# EPROM_Programmer_2.net
KiCad netlist of a schematic drawn in Altium Designer
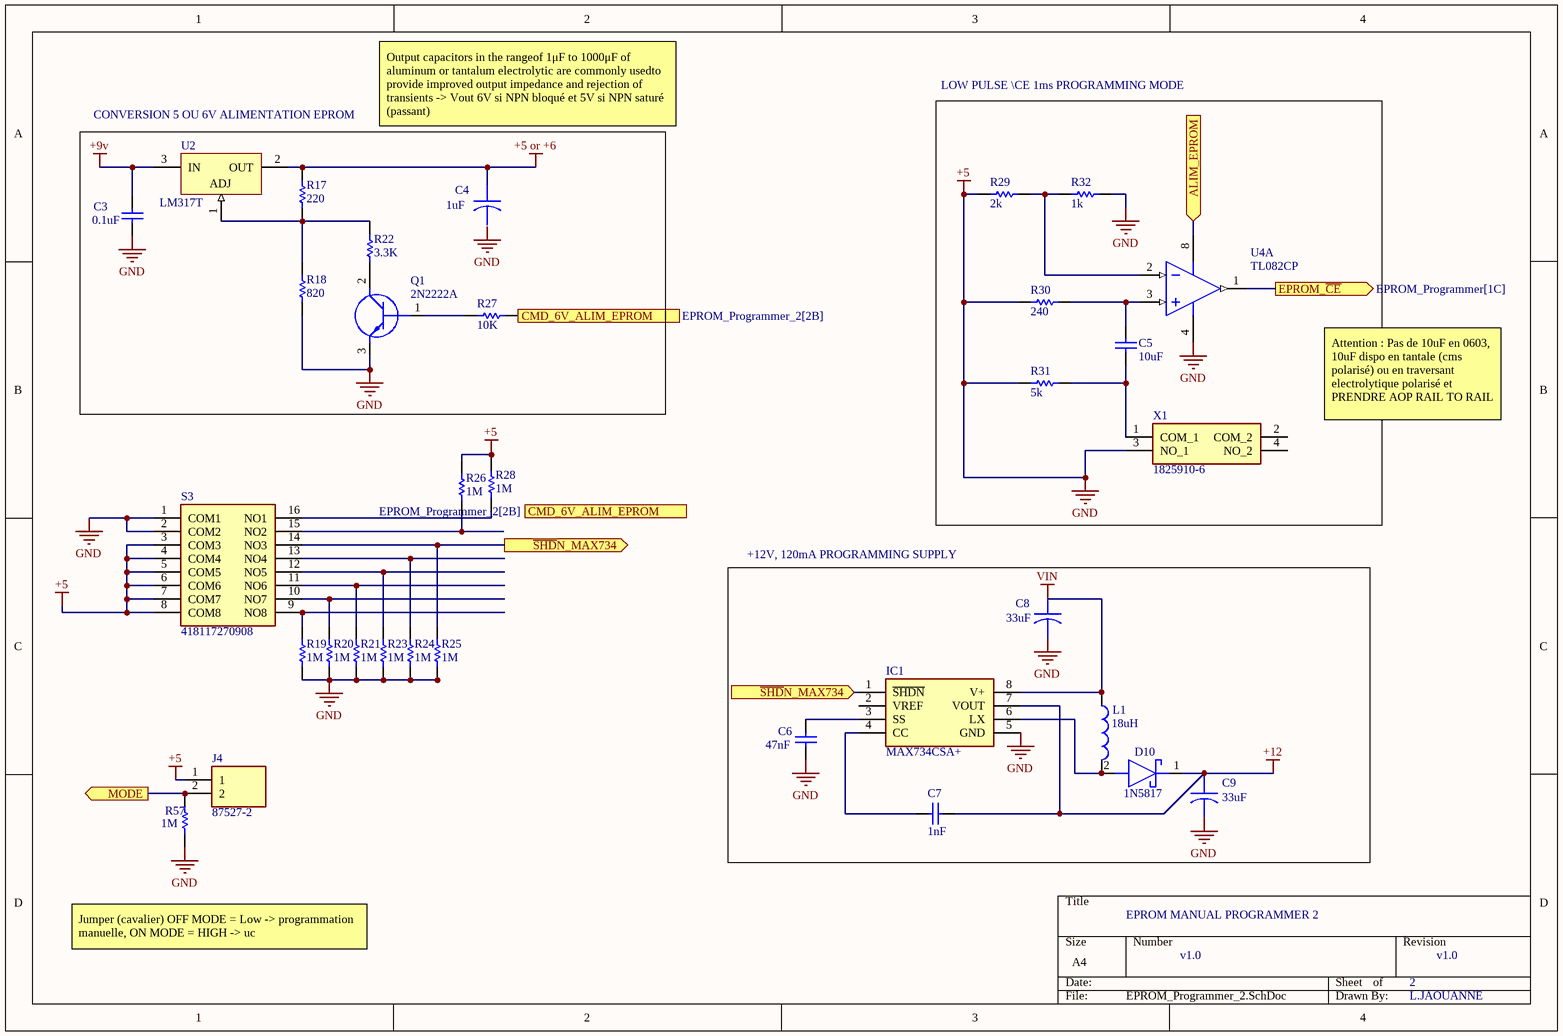
[diagram p0: EPROM_Programmer_2.SchDoc]

(export (version "E")
  (design (tool "Eeschema 10.0.6"))
  (components
    (comp (ref "C3")
      (value "0.1uF")
      (footprint "C0603")
      (description "Capacitor")
      (libsource (lib "Custom_Component") (part "Cap"))
    )
    (comp (ref "C4")
      (value "1uF")
      (footprint "CAPPRD200W50D550H1250:CAPPRD200W50D550H1250")
      (description "33ÂµF 16V Aluminum Electrolytic Capacitors Radial, Can 2000 Hrs @ 85Â°C")
      (fields (field (name "MP") "UVR1C330MDD") (field (name "MF") "Nichicon"))
      (libsource (lib "Capacitor-Electrolytic-33uF-16v-Radial") (part "UVR1C330MDD"))
    )
    (comp (ref "C5")
      (value "10uF")
      (footprint "C0603")
      (description "Capacitor")
      (libsource (lib "Custom_Component") (part "Cap"))
    )
    (comp (ref "C6")
      (value "47nF")
      (footprint "C0603")
      (description "Capacitor")
      (libsource (lib "Custom_Component") (part "Cap"))
    )
    (comp (ref "C7")
      (value "1nF")
      (footprint "C0603")
      (description "Capacitor")
      (libsource (lib "Custom_Component") (part "Cap"))
    )
    (comp (ref "C8")
      (value "33uF")
      (footprint "CAPPRD200W50D550H1250:CAPPRD200W50D550H1250")
      (description "33ÂµF 16V Aluminum Electrolytic Capacitors Radial, Can 2000 Hrs @ 85Â°C")
      (fields (field (name "MP") "UVR1C330MDD") (field (name "MF") "Nichicon"))
      (libsource (lib "Capacitor-Electrolytic-33uF-16v-Radial") (part "UVR1C330MDD"))
    )
    (comp (ref "C9")
      (value "33uF")
      (footprint "CAPPRD200W50D550H1250:CAPPRD200W50D550H1250")
      (description "33ÂµF 16V Aluminum Electrolytic Capacitors Radial, Can 2000 Hrs @ 85Â°C")
      (fields (field (name "MP") "UVR1C330MDD") (field (name "MF") "Nichicon"))
      (libsource (lib "Capacitor-Electrolytic-33uF-16v-Radial") (part "UVR1C330MDD"))
    )
    (comp (ref "D10")
      (value "1N5817")
      (footprint "SamacSys:DIOAD950W60L350D150")
      (description "Schottky Diode")
      (fields
        (field (name "MANUFACTURER_PART_NUMBER") "SD103A-TR")
        (field (name "MOUSER PART NUMBER") "625-SD103A")
      )
      (libsource (lib "SamacSys") (part "SD103A-TR"))
    )
    (comp (ref "IC1")
      (value "MAX734CSA+")
      (footprint "SamacSys:SOIC127P600X175-8N")
      (description "Integrated Circuit")
      (fields (field (name "MOUSER PART NUMBER") "700-MAX734CSA"))
      (libsource (lib "*") (part "MAX734CSA+"))
    )
    (comp (ref "J4")
      (value "87527-2")
      (footprint "SamacSys:HDRV2W66P0X254_1X2_467X244X1044P")
      (description "Connector Embases et logements de câbles HEADER 2 POS")
      (fields (field (name "MOUSER PART NUMBER") "571-875272"))
      (libsource (lib "*") (part "87527-2"))
    )
    (comp (ref "L1")
      (value "18uH")
      (footprint "2029")
      (description "Inductor")
      (libsource (lib "Custom_Component") (part "Inductor"))
    )
    (comp (ref "Q1")
      (value "2N2222A")
      (footprint "SamacSys:TO-18_4")
      (description "Transistor BJT NPN")
      (fields (field (name "MOUSER PART NUMBER") "511-2N2222A"))
      (libsource (lib "*") (part "2N2222A"))
    )
    (comp (ref "R17")
      (value "220")
      (footprint "R0603")
      (description "Resistor")
      (fields (field (name "Comment") "Res1"))
      (libsource (lib "Custom_Component") (part "Res1"))
    )
    (comp (ref "R18")
      (value "820")
      (footprint "R0603")
      (description "Resistor")
      (fields (field (name "Comment") "Res1"))
      (libsource (lib "Custom_Component") (part "Res1"))
    )
    (comp (ref "R19")
      (value "1M")
      (footprint "R0603")
      (description "Resistor")
      (fields (field (name "Comment") "Res1"))
      (libsource (lib "Custom_Component") (part "Res1"))
    )
    (comp (ref "R20")
      (value "1M")
      (footprint "R0603")
      (description "Resistor")
      (fields (field (name "Comment") "Res1"))
      (libsource (lib "Custom_Component") (part "Res1"))
    )
    (comp (ref "R21")
      (value "1M")
      (footprint "R0603")
      (description "Resistor")
      (fields (field (name "Comment") "Res1"))
      (libsource (lib "Custom_Component") (part "Res1"))
    )
    (comp (ref "R22")
      (value "3.3K")
      (footprint "R0603")
      (description "Resistor")
      (fields (field (name "Comment") "Res1"))
      (libsource (lib "Custom_Component") (part "Res1"))
    )
    (comp (ref "R23")
      (value "1M")
      (footprint "R0603")
      (description "Resistor")
      (fields (field (name "Comment") "Res1"))
      (libsource (lib "Custom_Component") (part "Res1"))
    )
    (comp (ref "R24")
      (value "1M")
      (footprint "R0603")
      (description "Resistor")
      (fields (field (name "Comment") "Res1"))
      (libsource (lib "Custom_Component") (part "Res1"))
    )
    (comp (ref "R25")
      (value "1M")
      (footprint "R0603")
      (description "Resistor")
      (fields (field (name "Comment") "Res1"))
      (libsource (lib "Custom_Component") (part "Res1"))
    )
    (comp (ref "R26")
      (value "1M")
      (footprint "R0603")
      (description "Resistor")
      (fields (field (name "Comment") "Res1"))
      (libsource (lib "Custom_Component") (part "Res1"))
    )
    (comp (ref "R27")
      (value "10K")
      (footprint "R0603")
      (description "Resistor")
      (fields (field (name "Comment") "Res1"))
      (libsource (lib "Custom_Component") (part "Res1"))
    )
    (comp (ref "R28")
      (value "1M")
      (footprint "R0603")
      (description "Resistor")
      (fields (field (name "Comment") "Res1"))
      (libsource (lib "Custom_Component") (part "Res1"))
    )
    (comp (ref "R29")
      (value "2k")
      (footprint "R0603")
      (description "Resistor")
      (fields (field (name "Comment") "Res1"))
      (libsource (lib "Custom_Component") (part "Res1"))
    )
    (comp (ref "R30")
      (value "240")
      (footprint "R0603")
      (description "Resistor")
      (fields (field (name "Comment") "Res1"))
      (libsource (lib "Custom_Component") (part "Res1"))
    )
    (comp (ref "R31")
      (value "5k")
      (footprint "R0603")
      (description "Resistor")
      (fields (field (name "Comment") "Res1"))
      (libsource (lib "Custom_Component") (part "Res1"))
    )
    (comp (ref "R32")
      (value "1k")
      (footprint "R0603")
      (description "Resistor")
      (fields (field (name "Comment") "Res1"))
      (libsource (lib "Custom_Component") (part "Res1"))
    )
    (comp (ref "R57")
      (value "1M")
      (footprint "R0603")
      (description "Resistor")
      (fields (field (name "Comment") "Res1"))
      (libsource (lib "Custom_Component") (part "Res1"))
    )
    (comp (ref "S3")
      (value "418117270908")
      (footprint "SamacSys:DIPS762W60P254L2132H695Q16N")
      (description "Switch")
      (fields (field (name "MOUSER PART NUMBER") "710-418117270908"))
      (libsource (lib "*") (part "418117270908"))
    )
    (comp (ref "U2")
      (value "LM317T")
      (footprint "TO254P1054X470X1955-3:TO254P1054X470X1955-3")
      (description "1.5A, 1.2V to 37V Adjustable Voltage Regulator, 3-Pin TO-220")
      (libsource (lib "LM317T_STMicro") (part "CMP-0244-00444-1"))
    )
    (comp (ref "U4")
      (value "TL082CP")
      (footprint "P0008A")
      (description "JFET-Input Operational Amplifier, 7 to 36 V, 0 to 70 degC, 8-pin DIP (P8), Pb-Free (RoHS)")
      (fields (field (name "MANUFACTURER") "Texas Instruments"))
      (libsource (lib "TL082CP_TI") (part "CMP-0055-00158-5"))
    )
    (comp (ref "X1")
      (value "1825910-6")
      (footprint "18259106")
      (description "Body Features: Product Orientation Vertical")
      (fields (field (name "MOUSER PART NUMBER") "650-1825910-6"))
      (libsource (lib "1825910-6") (part "1825910-6"))
    )
  )
  (nets
    (net (code "1") (name "+5") (class "Default")
      (node (ref "C3") (pin "2") (pinfunction "2_2") (pintype "passive"))
      (node (ref "C6") (pin "2") (pinfunction "2_2") (pintype "passive"))
      (node (ref "C8") (pin "2") (pinfunction "2_2") (pintype "passive"))
      (node (ref "C9") (pin "2") (pinfunction "2_2") (pintype "passive"))
      (node (ref "IC1") (pin "5") (pinfunction "GND_5") (pintype "passive"))
      (node (ref "J4") (pin "1") (pinfunction "1_1") (pintype "passive"))
      (node (ref "Q1") (pin "3") (pinfunction "E_3") (pintype "passive"))
      (node (ref "R18") (pin "2") (pinfunction "2_2") (pintype "passive"))
      (node (ref "R19") (pin "2") (pinfunction "2_2") (pintype "passive"))
      (node (ref "R20") (pin "2") (pinfunction "2_2") (pintype "passive"))
      (node (ref "R21") (pin "2") (pinfunction "2_2") (pintype "passive"))
      (node (ref "R23") (pin "2") (pinfunction "2_2") (pintype "passive"))
      (node (ref "R24") (pin "2") (pinfunction "2_2") (pintype "passive"))
      (node (ref "R25") (pin "2") (pinfunction "2_2") (pintype "passive"))
      (node (ref "R26") (pin "1") (pinfunction "1_1") (pintype "passive"))
      (node (ref "R28") (pin "1") (pinfunction "1_1") (pintype "passive"))
      (node (ref "R29") (pin "2") (pinfunction "2_2") (pintype "passive"))
      (node (ref "R30") (pin "2") (pinfunction "2_2") (pintype "passive"))
      (node (ref "R31") (pin "2") (pinfunction "2_2") (pintype "passive"))
      (node (ref "R32") (pin "1") (pinfunction "1_1") (pintype "passive"))
      (node (ref "R57") (pin "2") (pinfunction "2_2") (pintype "passive"))
      (node (ref "S3") (pin "1") (pinfunction "COM1_1") (pintype "passive"))
      (node (ref "S3") (pin "2") (pinfunction "COM2_2") (pintype "passive"))
      (node (ref "S3") (pin "3") (pinfunction "COM3_3") (pintype "passive"))
      (node (ref "S3") (pin "4") (pinfunction "COM4_4") (pintype "passive"))
      (node (ref "S3") (pin "5") (pinfunction "COM5_5") (pintype "passive"))
      (node (ref "S3") (pin "6") (pinfunction "COM6_6") (pintype "passive"))
      (node (ref "S3") (pin "7") (pinfunction "COM7_7") (pintype "passive"))
      (node (ref "S3") (pin "8") (pinfunction "COM8_8") (pintype "passive"))
      (node (ref "U4") (pin "4") (pinfunction "VCC-_4") (pintype "power_in"))
      (node (ref "X1") (pin "3") (pinfunction "NO_1_3") (pintype "passive"))
    )
    (net (code "2") (name "+5 or +6") (class "Default")
      (node (ref "C4") (pin "1") (pinfunction "1_1") (pintype "passive"))
      (node (ref "R17") (pin "2") (pinfunction "2_2") (pintype "passive"))
      (node (ref "U2") (pin "2") (pinfunction "OUT_2") (pintype "power_in"))
    )
    (net (code "3") (name "+9v") (class "Default")
      (node (ref "C3") (pin "1") (pinfunction "1_1") (pintype "passive"))
      (node (ref "U2") (pin "3") (pinfunction "IN_3") (pintype "power_in"))
    )
    (net (code "4") (name "+12") (class "Default")
      (node (ref "C7") (pin "2") (pinfunction "2_2") (pintype "passive"))
      (node (ref "C9") (pin "1") (pinfunction "1_1") (pintype "passive"))
      (node (ref "D10") (pin "1") (pinfunction "K_1") (pintype "passive"))
      (node (ref "IC1") (pin "7") (pinfunction "VOUT_7") (pintype "passive"))
    )
    (net (code "5") (name "/ALIM_EPROM") (class "Default")
      (node (ref "U4") (pin "8") (pinfunction "VCC+_8") (pintype "power_in"))
    )
    (net (code "6") (name "/CMD_6V_ALIM_EPROM") (class "Default")
      (node (ref "R27") (pin "1") (pinfunction "1_1") (pintype "passive"))
    )
    (net (code "7") (name "/EPROM_~{CE}") (class "Default")
      (node (ref "U4") (pin "1") (pinfunction "OUT1_1") (pintype "output"))
    )
    (net (code "8") (name "/MODE") (class "Default")
      (node (ref "J4") (pin "2") (pinfunction "2_2") (pintype "passive"))
      (node (ref "R57") (pin "1") (pinfunction "1_1") (pintype "passive"))
    )
    (net (code "9") (name "/~{SHD}N_MAX734") (class "Default")
      (node (ref "IC1") (pin "1") (pinfunction "~{SHDN}_1") (pintype "passive"))
      (node (ref "R25") (pin "1") (pinfunction "1_1") (pintype "passive"))
      (node (ref "S3") (pin "14") (pinfunction "NO3_14") (pintype "passive"))
    )
    (net (code "10") (name "Net-(D10-A)") (class "Default")
      (node (ref "D10") (pin "2") (pinfunction "A_2") (pintype "passive"))
      (node (ref "IC1") (pin "6") (pinfunction "LX_6") (pintype "passive"))
      (node (ref "L1") (pin "2") (pinfunction "2_2") (pintype "passive"))
    )
    (net (code "11") (name "Net-(IC1-CC)") (class "Default")
      (node (ref "C7") (pin "1") (pinfunction "1_1") (pintype "passive"))
      (node (ref "IC1") (pin "4") (pinfunction "CC_4") (pintype "passive"))
    )
    (net (code "12") (name "Net-(IC1-SS)") (class "Default")
      (node (ref "C6") (pin "1") (pinfunction "1_1") (pintype "passive"))
      (node (ref "IC1") (pin "3") (pinfunction "SS_3") (pintype "passive"))
    )
    (net (code "13") (name "Net-(IC1-V+)") (class "Default")
      (node (ref "IC1") (pin "8") (pinfunction "V+_8") (pintype "passive"))
      (node (ref "L1") (pin "1") (pinfunction "1_1") (pintype "passive"))
    )
    (net (code "14") (name "Net-(Q1-B)") (class "Default")
      (node (ref "Q1") (pin "1") (pinfunction "B_1") (pintype "passive"))
      (node (ref "R27") (pin "2") (pinfunction "2_2") (pintype "passive"))
    )
    (net (code "15") (name "Net-(Q1-C)") (class "Default")
      (node (ref "Q1") (pin "2") (pinfunction "C_2") (pintype "passive"))
      (node (ref "R22") (pin "2") (pinfunction "2_2") (pintype "passive"))
    )
    (net (code "16") (name "Net-(S3-NO1)") (class "Default")
      (node (ref "R28") (pin "2") (pinfunction "2_2") (pintype "passive"))
      (node (ref "S3") (pin "16") (pinfunction "NO1_16") (pintype "passive"))
    )
    (net (code "17") (name "Net-(S3-NO2)") (class "Default")
      (node (ref "R26") (pin "2") (pinfunction "2_2") (pintype "passive"))
      (node (ref "S3") (pin "15") (pinfunction "NO2_15") (pintype "passive"))
    )
    (net (code "18") (name "Net-(S3-NO4)") (class "Default")
      (node (ref "R24") (pin "1") (pinfunction "1_1") (pintype "passive"))
      (node (ref "S3") (pin "13") (pinfunction "NO4_13") (pintype "passive"))
    )
    (net (code "19") (name "Net-(S3-NO5)") (class "Default")
      (node (ref "R23") (pin "1") (pinfunction "1_1") (pintype "passive"))
      (node (ref "S3") (pin "12") (pinfunction "NO5_12") (pintype "passive"))
    )
    (net (code "20") (name "Net-(S3-NO6)") (class "Default")
      (node (ref "R21") (pin "1") (pinfunction "1_1") (pintype "passive"))
      (node (ref "S3") (pin "11") (pinfunction "NO6_11") (pintype "passive"))
    )
    (net (code "21") (name "Net-(S3-NO7)") (class "Default")
      (node (ref "R20") (pin "1") (pinfunction "1_1") (pintype "passive"))
      (node (ref "S3") (pin "10") (pinfunction "NO7_10") (pintype "passive"))
    )
    (net (code "22") (name "Net-(S3-NO8)") (class "Default")
      (node (ref "R19") (pin "1") (pinfunction "1_1") (pintype "passive"))
      (node (ref "S3") (pin "9") (pinfunction "NO8_9") (pintype "passive"))
    )
    (net (code "23") (name "Net-(U2-ADJ)") (class "Default")
      (node (ref "R17") (pin "1") (pinfunction "1_1") (pintype "passive"))
      (node (ref "R18") (pin "1") (pinfunction "1_1") (pintype "passive"))
      (node (ref "R22") (pin "1") (pinfunction "1_1") (pintype "passive"))
      (node (ref "U2") (pin "1") (pinfunction "ADJ_1") (pintype "input"))
    )
    (net (code "24") (name "Net-(U4A-IN1+)") (class "Default")
      (node (ref "C5") (pin "1") (pinfunction "1_1") (pintype "passive"))
      (node (ref "R30") (pin "1") (pinfunction "1_1") (pintype "passive"))
      (node (ref "U4") (pin "3") (pinfunction "IN1+_3") (pintype "input"))
    )
    (net (code "25") (name "Net-(U4A-IN1-)") (class "Default")
      (node (ref "R29") (pin "1") (pinfunction "1_1") (pintype "passive"))
      (node (ref "R32") (pin "2") (pinfunction "2_2") (pintype "passive"))
      (node (ref "U4") (pin "2") (pinfunction "IN1-_2") (pintype "input"))
    )
    (net (code "26") (name "Net-(X1-COM_1)") (class "Default")
      (node (ref "C5") (pin "2") (pinfunction "2_2") (pintype "passive"))
      (node (ref "R31") (pin "1") (pinfunction "1_1") (pintype "passive"))
      (node (ref "X1") (pin "1") (pinfunction "COM_1_1") (pintype "passive"))
    )
    (net (code "27") (name "VIN") (class "Default")
      (node (ref "C8") (pin "1") (pinfunction "1_1") (pintype "passive"))
    )
    (net (code "28") (name "unconnected-(C4-Pad2)") (class "Default")
      (node (ref "C4") (pin "2") (pinfunction "2_2") (pintype "passive"))
    )
    (net (code "29") (name "unconnected-(IC1-VREF-Pad2)") (class "Default")
      (node (ref "IC1") (pin "2") (pinfunction "VREF_2") (pintype "passive"))
    )
    (net (code "30") (name "unconnected-(X1-COM_2-Pad2)") (class "Default")
      (node (ref "X1") (pin "2") (pinfunction "COM_2_2") (pintype "passive"))
    )
    (net (code "31") (name "unconnected-(X1-NO_2-Pad4)") (class "Default")
      (node (ref "X1") (pin "4") (pinfunction "NO_2_4") (pintype "passive"))
    )
  )
)
